# Sheet1.net
KiCad netlist of a schematic drawn in Altium Designer
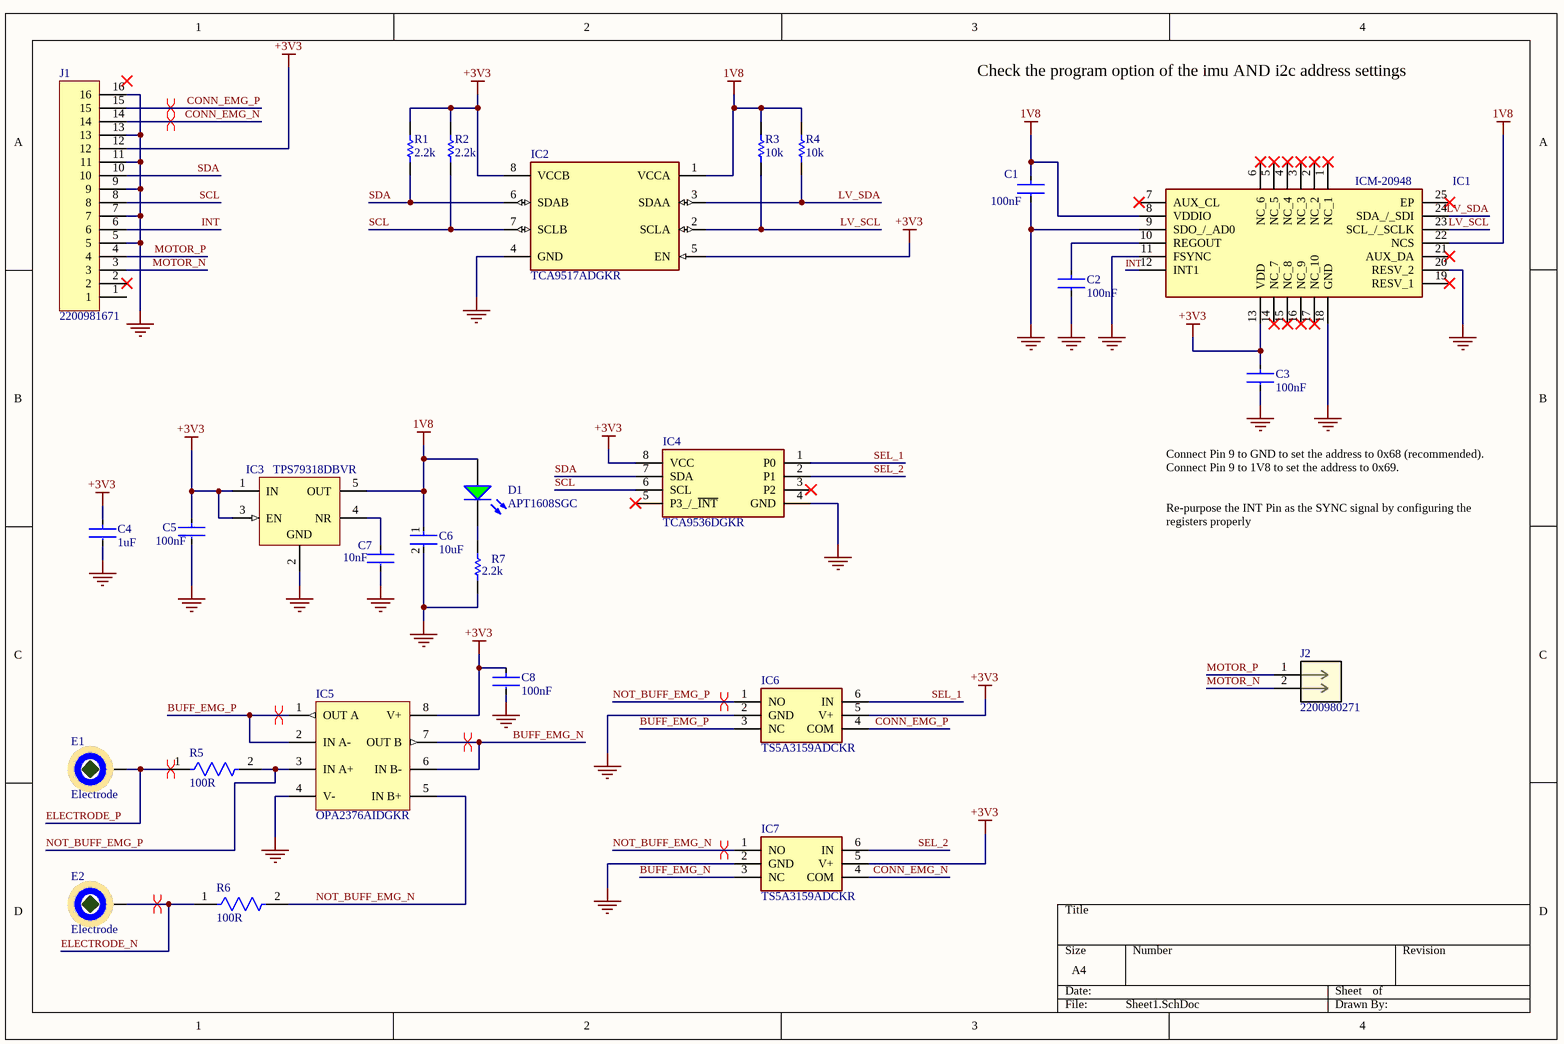
[diagram p0: Sheet1.SchDoc]

(export (version "E")
  (design (tool "Eeschema 10.0.6"))
  (components
    (comp (ref "C1")
      (value "100nF")
      (footprint "FP-CC0603-DA-MFG")
      (description "100nF 50V X7R ±10% 0603 Multilayer Ceramic Capacitors MLCC - SMD/SMT ROHS")
      (fields (field (name "MANUFACTURER") "YAGEO") (field (name "VOLTAGE") "50 V"))
      (libsource (lib "Altium Content Vault") (part "11868f565c42a9108669ba33697ecf6"))
    )
    (comp (ref "C2")
      (value "100nF")
      (footprint "FP-CC0603-DA-MFG")
      (description "100nF 50V X7R ±10% 0603 Multilayer Ceramic Capacitors MLCC - SMD/SMT ROHS")
      (fields (field (name "MANUFACTURER") "YAGEO") (field (name "VOLTAGE") "50 V"))
      (libsource (lib "Altium Content Vault") (part "11868f565c42a9108669ba33697ecf6"))
    )
    (comp (ref "C3")
      (value "100nF")
      (footprint "FP-CC0603-DA-MFG")
      (description "100nF 50V X7R ±10% 0603 Multilayer Ceramic Capacitors MLCC - SMD/SMT ROHS")
      (fields (field (name "MANUFACTURER") "YAGEO") (field (name "VOLTAGE") "50 V"))
      (libsource (lib "Altium Content Vault") (part "11868f565c42a9108669ba33697ecf6"))
    )
    (comp (ref "C4")
      (value "1uF")
      (footprint "FP-C0402C-BB-IPC_B")
      (description "CAP CER 1UF 16V X5R 0402")
      (fields (field (name "TOLERANCE") "10%") (field (name "MPN") "C0402C105K4PACTU"))
      (libsource (lib "Altium Content Vault") (part "b4654b650e69147ec39a6b967a45e02"))
    )
    (comp (ref "C5")
      (value "100nF")
      (footprint "FP-GRM155-0_05-MFG")
      (description "Chip Multilayer Ceramic Capacitors for General Purpose, 0402, 0.10uF, X7S, 22%, 10%, 50V")
      (fields (field (name "TOLERANCE") "10%") (field (name "MPN") "GRM155C71H104KE19D"))
      (libsource (lib "Altium Content Vault") (part "02cd4be3c70576c341d710602a673aa"))
    )
    (comp (ref "C6")
      (value "10uF")
      (footprint "FP-GRM155-0_2-IPC_A")
      (description "Chip Multilayer Ceramic Capacitors for General Purpose, 0402, 10uF, X5R, 15%, 20%, 10V")
      (fields (field (name "MPN") "GRM155R61A106ME11D"))
      (libsource (lib "") (part "b4654b650e69147ec39a6b967a45e02_1"))
    )
    (comp (ref "C7")
      (value "10nF")
      (footprint "FP-C0402-BB-MFG")
      (description "C0402 10,000 pF X7R 10.00% 50 V")
      (fields
        (field (name "OCTOPART") "https://octopart.com/c0402c103k5rac7411-kemet-25528449")
        (field (name "TOLERANCE") "0.1")
      )
      (libsource (lib "Altium Content Vault") (part "b4654b650e69147ec39a6b967a45e02"))
    )
    (comp (ref "C8")
      (value "100nF")
      (footprint "FP-CC0603-DA-MFG")
      (description "100nF 50V X7R ±10% 0603 Multilayer Ceramic Capacitors MLCC - SMD/SMT ROHS")
      (fields (field (name "MANUFACTURER") "YAGEO") (field (name "VOLTAGE") "50 V"))
      (libsource (lib "Altium Content Vault") (part "11868f565c42a9108669ba33697ecf6"))
    )
    (comp (ref "D1")
      (value "APT1608SGC")
      (footprint "KING-APT1608SGC_V")
      (description "Super Bright Green LED, 62.5 mW, 25 mA, -40 to 85 degC, 2-Pin SMD, RoHS, Tape and Reel")
      (fields (field (name "MANUFACTURER") "Kingbright"))
      (libsource (lib "Altium Content Vault") (part "LED-GREEN-AK-2"))
    )
    (comp (ref "E1")
      (value "Electrode")
      (footprint "Electrode")
      (libsource (lib "Sensor_node") (part "Electrode"))
    )
    (comp (ref "E2")
      (value "Electrode")
      (footprint "Electrode")
      (libsource (lib "Sensor_node") (part "Electrode"))
    )
    (comp (ref "IC1")
      (value "ICM-20948")
      (footprint "SamacSys:QFN40P300X300X105-25N-D")
      (description "Integrated Circuit")
      (fields (field (name "MOUSER PART NUMBER") "410-ICM-20948"))
      (libsource (lib "*") (part "ICM-20948"))
    )
    (comp (ref "IC2")
      (value "TCA9517ADGKR")
      (footprint "FP-DGK0008A-IPC_C")
      (description "IC TRNSLTR BIDIRECTIONAL 8VSSOP")
      (libsource (lib "Altium Content Vault") (part "376f503177af6135b4bcb823927ec01"))
    )
    (comp (ref "IC3")
      (value "TPS79318DBVR")
      (footprint "DBV0005A_M")
      (fields (field (name "MANUFACTURER") "Texas Instruments"))
      (libsource (lib "Altium Content Vault") (part "TI-TPS79NXX-YYSOT5"))
    )
    (comp (ref "IC4")
      (value "TCA9536DGKR")
      (footprint "SamacSys:SOP65P490X110-8N")
      (description "Integrated Circuit")
      (fields (field (name "MOUSER PART NUMBER") "595-TCA9536DGKR"))
      (libsource (lib "*") (part "TCA9536DGKR"))
    )
    (comp (ref "IC5")
      (value "OPA2376AIDGKR")
      (footprint "OPA2376")
      (description "IC OPAMP GP 2 CIRCUIT 8VSSOP")
      (libsource (lib "Sensor_node") (part "OPA2376AIDGKR"))
    )
    (comp (ref "IC6")
      (value "TS5A3159ADCKR")
      (footprint "SamacSys:SOT65P210X110-6N")
      (description "IC SWITCH SPDTX1 900MOHM SC70-6")
      (fields (field (name "MOUSER PART NUMBER") "595-TS5A3159ADCKR"))
      (libsource (lib "*") (part "TS5A3159ADCKR"))
    )
    (comp (ref "IC7")
      (value "TS5A3159ADCKR")
      (footprint "SamacSys:SOT65P210X110-6N")
      (description "IC SWITCH SPDTX1 900MOHM SC70-6")
      (fields (field (name "MOUSER PART NUMBER") "595-TS5A3159ADCKR"))
      (libsource (lib "*") (part "TS5A3159ADCKR"))
    )
    (comp (ref "J1")
      (value "2200981671")
      (footprint "CONN_2200980000-SD_16_MOL")
      (description "Connector Header Through Hole, Right Angle 16 position 0.049\" (1.25mm)")
      (libsource (lib "Sensor_node") (part "2200981671"))
    )
    (comp (ref "J2")
      (value "2200980271")
      (footprint "2X1_right_angle_THT_CON")
      (description "Molex connector")
      (libsource (lib "Sensor_node") (part "2X1_RHTANG_HDR"))
    )
    (comp (ref "R1")
      (value "2.2k")
      (footprint "RESC0402(1005)_N")
      (description "2K2 0.063W 5% 0402 (1005 Metric)  SMD")
      (fields (field (name "TOLERANCE") "5 %") (field (name "POWER") "0.063 W"))
      (libsource (lib "Altium Content Vault") (part "RES"))
    )
    (comp (ref "R2")
      (value "2.2k")
      (footprint "RESC0402(1005)_N")
      (description "2K2 0.063W 5% 0402 (1005 Metric)  SMD")
      (fields (field (name "TOLERANCE") "5 %") (field (name "POWER") "0.063 W"))
      (libsource (lib "Altium Content Vault") (part "RES"))
    )
    (comp (ref "R3")
      (value "10k")
      (footprint "RESC1005X40X20NL05T10")
      (fields
        (field (name "MANUFACTURER") "Vishay BCcomponents")
        (field (name "PART NUMBER") "TNPW040210K0DEED")
      )
      (libsource (lib "Altium Content Vault") (part "RES"))
    )
    (comp (ref "R4")
      (value "10k")
      (footprint "RESC1005X40X20NL05T10")
      (fields
        (field (name "MANUFACTURER") "Vishay BCcomponents")
        (field (name "PART NUMBER") "TNPW040210K0DEED")
      )
      (libsource (lib "Altium Content Vault") (part "RES"))
    )
    (comp (ref "R5")
      (value "100R")
      (footprint "FP-MCS0402-IPC_B")
      (description "RES SMD 1.2K OHM 1% 1/10W 0402")
      (fields (field (name "TOLERANCE") "0.5%") (field (name "MPN") "MCS0402MD1000DE000"))
      (libsource (lib "Altium Content Vault") (part "1029c3af85768c4190bb7ad29bc67b5"))
    )
    (comp (ref "R6")
      (value "100R")
      (footprint "FP-MCS0402-IPC_B")
      (description "RES SMD 1.2K OHM 1% 1/10W 0402")
      (fields (field (name "TOLERANCE") "0.5%") (field (name "MPN") "MCS0402MD1000DE000"))
      (libsource (lib "Altium Content Vault") (part "1029c3af85768c4190bb7ad29bc67b5"))
    )
    (comp (ref "R7")
      (value "2.2k")
      (footprint "RESC0402(1005)_N")
      (description "2K2 0.063W 5% 0402 (1005 Metric)  SMD")
      (fields (field (name "TOLERANCE") "5 %") (field (name "POWER") "0.063 W"))
      (libsource (lib "Altium Content Vault") (part "RES"))
    )
  )
  (nets
    (net (code "1") (name "+3V3") (class "Default")
      (node (ref "C3") (pin "1") (pinfunction "1_1") (pintype "passive"))
      (node (ref "C4") (pin "1") (pinfunction "1_1") (pintype "passive"))
      (node (ref "C5") (pin "1") (pinfunction "1_1") (pintype "passive"))
      (node (ref "C8") (pin "1") (pinfunction "1_1") (pintype "passive"))
      (node (ref "IC1") (pin "13") (pinfunction "VDD_13") (pintype "passive"))
      (node (ref "IC2") (pin "5") (pinfunction "EN_5") (pintype "input"))
      (node (ref "IC2") (pin "8") (pinfunction "VCCB_8") (pintype "power_in"))
      (node (ref "IC3") (pin "1") (pinfunction "IN_1") (pintype "power_in"))
      (node (ref "IC3") (pin "3") (pinfunction "EN_3") (pintype "input"))
      (node (ref "IC4") (pin "8") (pinfunction "VCC_8") (pintype "passive"))
      (node (ref "IC5") (pin "8") (pinfunction "V+_8") (pintype "power_in"))
      (node (ref "IC6") (pin "5") (pinfunction "V+_5") (pintype "passive"))
      (node (ref "IC7") (pin "5") (pinfunction "V+_5") (pintype "passive"))
      (node (ref "J1") (pin "12") (pinfunction "12_12") (pintype "passive"))
      (node (ref "R1") (pin "2") (pinfunction "2_2") (pintype "passive"))
      (node (ref "R2") (pin "2") (pinfunction "2_2") (pintype "passive"))
    )
    (net (code "2") (name "/BUFF_EMG_N") (class "Default")
      (node (ref "IC5") (pin "6") (pinfunction "IN_B-_6") (pintype "passive"))
      (node (ref "IC5") (pin "7") (pinfunction "OUT_B_7") (pintype "output"))
      (node (ref "IC7") (pin "3") (pinfunction "NC_3") (pintype "passive"))
    )
    (net (code "3") (name "/BUFF_EMG_P") (class "Default")
      (node (ref "IC5") (pin "1") (pinfunction "OUT_A_1") (pintype "output"))
      (node (ref "IC5") (pin "2") (pinfunction "IN_A-_2") (pintype "passive"))
      (node (ref "IC6") (pin "3") (pinfunction "NC_3") (pintype "passive"))
    )
    (net (code "4") (name "/CONN_EMG_N") (class "Default")
      (node (ref "IC7") (pin "4") (pinfunction "COM_4") (pintype "passive"))
      (node (ref "J1") (pin "14") (pinfunction "14_14") (pintype "passive"))
    )
    (net (code "5") (name "/CONN_EMG_P") (class "Default")
      (node (ref "IC6") (pin "4") (pinfunction "COM_4") (pintype "passive"))
      (node (ref "J1") (pin "15") (pinfunction "15_15") (pintype "passive"))
    )
    (net (code "6") (name "/ELECTRODE_N") (class "Default")
      (node (ref "E2") (pin "1") (pinfunction "1_1") (pintype "passive"))
      (node (ref "R6") (pin "1") (pinfunction "1_1") (pintype "passive"))
    )
    (net (code "7") (name "/ELECTRODE_P") (class "Default")
      (node (ref "E1") (pin "1") (pinfunction "1_1") (pintype "passive"))
      (node (ref "R5") (pin "1") (pinfunction "1_1") (pintype "passive"))
    )
    (net (code "8") (name "/INT") (class "Default")
      (node (ref "IC1") (pin "12") (pinfunction "INT1_12") (pintype "passive"))
      (node (ref "J1") (pin "6") (pinfunction "6_6") (pintype "passive"))
    )
    (net (code "9") (name "/LV_SCL") (class "Default")
      (node (ref "IC1") (pin "23") (pinfunction "SCL_/_SCLK_23") (pintype "passive"))
      (node (ref "IC2") (pin "2") (pinfunction "SCLA_2") (pintype "bidirectional"))
      (node (ref "R3") (pin "1") (pinfunction "1_1") (pintype "passive"))
    )
    (net (code "10") (name "/LV_SDA") (class "Default")
      (node (ref "IC1") (pin "24") (pinfunction "SDA_/_SDI_24") (pintype "passive"))
      (node (ref "IC2") (pin "3") (pinfunction "SDAA_3") (pintype "bidirectional"))
      (node (ref "R4") (pin "1") (pinfunction "1_1") (pintype "passive"))
    )
    (net (code "11") (name "/MOTOR_N") (class "Default")
      (node (ref "J1") (pin "3") (pinfunction "3_3") (pintype "passive"))
      (node (ref "J2") (pin "2") (pinfunction "2_2") (pintype "passive"))
    )
    (net (code "12") (name "/MOTOR_P") (class "Default")
      (node (ref "J1") (pin "4") (pinfunction "4_4") (pintype "passive"))
      (node (ref "J2") (pin "1") (pinfunction "1_1") (pintype "passive"))
    )
    (net (code "13") (name "/NOT_BUFF_EMG_N") (class "Default")
      (node (ref "IC5") (pin "5") (pinfunction "IN_B+_5") (pintype "passive"))
      (node (ref "IC7") (pin "1") (pinfunction "NO_1") (pintype "passive"))
      (node (ref "R6") (pin "2") (pinfunction "2_2") (pintype "passive"))
    )
    (net (code "14") (name "/NOT_BUFF_EMG_P") (class "Default")
      (node (ref "IC5") (pin "3") (pinfunction "IN_A+_3") (pintype "passive"))
      (node (ref "IC6") (pin "1") (pinfunction "NO_1") (pintype "passive"))
      (node (ref "R5") (pin "2") (pinfunction "2_2") (pintype "passive"))
    )
    (net (code "15") (name "/SCL") (class "Default")
      (node (ref "IC2") (pin "7") (pinfunction "SCLB_7") (pintype "bidirectional"))
      (node (ref "IC4") (pin "6") (pinfunction "SCL_6") (pintype "passive"))
      (node (ref "J1") (pin "8") (pinfunction "8_8") (pintype "passive"))
      (node (ref "R2") (pin "1") (pinfunction "1_1") (pintype "passive"))
    )
    (net (code "16") (name "/SDA") (class "Default")
      (node (ref "IC2") (pin "6") (pinfunction "SDAB_6") (pintype "bidirectional"))
      (node (ref "IC4") (pin "7") (pinfunction "SDA_7") (pintype "passive"))
      (node (ref "J1") (pin "10") (pinfunction "10_10") (pintype "passive"))
      (node (ref "R1") (pin "1") (pinfunction "1_1") (pintype "passive"))
    )
    (net (code "17") (name "/SEL_1") (class "Default")
      (node (ref "IC4") (pin "1") (pinfunction "P0_1") (pintype "passive"))
      (node (ref "IC6") (pin "6") (pinfunction "IN_6") (pintype "passive"))
    )
    (net (code "18") (name "/SEL_2") (class "Default")
      (node (ref "IC4") (pin "2") (pinfunction "P1_2") (pintype "passive"))
      (node (ref "IC7") (pin "6") (pinfunction "IN_6") (pintype "passive"))
    )
    (net (code "19") (name "1V8") (class "Default")
      (node (ref "C1") (pin "1") (pinfunction "1_1") (pintype "passive"))
      (node (ref "C6") (pin "1") (pinfunction "1_1") (pintype "passive"))
      (node (ref "D1") (pin "1") (pinfunction "A_1") (pintype "passive"))
      (node (ref "IC1") (pin "22") (pinfunction "NCS_22") (pintype "passive"))
      (node (ref "IC1") (pin "8") (pinfunction "VDDIO_8") (pintype "passive"))
      (node (ref "IC2") (pin "1") (pinfunction "VCCA_1") (pintype "power_in"))
      (node (ref "IC3") (pin "5") (pinfunction "OUT_5") (pintype "power_in"))
      (node (ref "R3") (pin "2") (pinfunction "2_2") (pintype "passive"))
      (node (ref "R4") (pin "2") (pinfunction "2_2") (pintype "passive"))
    )
    (net (code "20") (name "GND") (class "Default")
      (node (ref "C1") (pin "2") (pinfunction "2_2") (pintype "passive"))
      (node (ref "C2") (pin "2") (pinfunction "2_2") (pintype "passive"))
      (node (ref "C3") (pin "2") (pinfunction "2_2") (pintype "passive"))
      (node (ref "C4") (pin "2") (pinfunction "2_2") (pintype "passive"))
      (node (ref "C5") (pin "2") (pinfunction "2_2") (pintype "passive"))
      (node (ref "C6") (pin "2") (pinfunction "2_2") (pintype "passive"))
      (node (ref "C7") (pin "2") (pinfunction "2_2") (pintype "passive"))
      (node (ref "C8") (pin "2") (pinfunction "2_2") (pintype "passive"))
      (node (ref "IC1") (pin "11") (pinfunction "FSYNC_11") (pintype "passive"))
      (node (ref "IC1") (pin "18") (pinfunction "GND_18") (pintype "passive"))
      (node (ref "IC1") (pin "20") (pinfunction "RESV_2_20") (pintype "passive"))
      (node (ref "IC1") (pin "9") (pinfunction "SDO_/_AD0_9") (pintype "passive"))
      (node (ref "IC2") (pin "4") (pinfunction "GND_4") (pintype "power_in"))
      (node (ref "IC3") (pin "2") (pinfunction "GND_2") (pintype "power_in"))
      (node (ref "IC4") (pin "4") (pinfunction "GND_4") (pintype "passive"))
      (node (ref "IC5") (pin "4") (pinfunction "V-_4") (pintype "power_in"))
      (node (ref "IC6") (pin "2") (pinfunction "GND_2") (pintype "passive"))
      (node (ref "IC7") (pin "2") (pinfunction "GND_2") (pintype "passive"))
      (node (ref "J1") (pin "11") (pinfunction "11_11") (pintype "passive"))
      (node (ref "J1") (pin "13") (pinfunction "13_13") (pintype "passive"))
      (node (ref "J1") (pin "16") (pinfunction "16_16") (pintype "passive"))
      (node (ref "J1") (pin "5") (pinfunction "5_5") (pintype "passive"))
      (node (ref "J1") (pin "7") (pinfunction "7_7") (pintype "passive"))
      (node (ref "J1") (pin "9") (pinfunction "9_9") (pintype "passive"))
      (node (ref "R7") (pin "1") (pinfunction "1_1") (pintype "passive"))
    )
    (net (code "21") (name "Net-(D1-K)") (class "Default")
      (node (ref "D1") (pin "2") (pinfunction "K_2") (pintype "passive"))
      (node (ref "R7") (pin "2") (pinfunction "2_2") (pintype "passive"))
    )
    (net (code "22") (name "Net-(IC1-REGOUT)") (class "Default")
      (node (ref "C2") (pin "1") (pinfunction "1_1") (pintype "passive"))
      (node (ref "IC1") (pin "10") (pinfunction "REGOUT_10") (pintype "passive"))
    )
    (net (code "23") (name "Net-(IC3-NR)") (class "Default")
      (node (ref "C7") (pin "1") (pinfunction "1_1") (pintype "passive"))
      (node (ref "IC3") (pin "4") (pinfunction "NR_4") (pintype "passive"))
    )
    (net (code "24") (name "unconnected-(IC1-AUX_CL-Pad7)") (class "Default")
      (node (ref "IC1") (pin "7") (pinfunction "AUX_CL_7") (pintype "passive+no_connect"))
    )
    (net (code "25") (name "unconnected-(IC1-AUX_DA-Pad21)") (class "Default")
      (node (ref "IC1") (pin "21") (pinfunction "AUX_DA_21") (pintype "passive+no_connect"))
    )
    (net (code "26") (name "unconnected-(IC1-EP-Pad25)") (class "Default")
      (node (ref "IC1") (pin "25") (pinfunction "EP_25") (pintype "passive+no_connect"))
    )
    (net (code "27") (name "unconnected-(IC1-NC_1-Pad1)") (class "Default")
      (node (ref "IC1") (pin "1") (pinfunction "NC_1_1") (pintype "passive+no_connect"))
    )
    (net (code "28") (name "unconnected-(IC1-NC_2-Pad2)") (class "Default")
      (node (ref "IC1") (pin "2") (pinfunction "NC_2_2") (pintype "passive+no_connect"))
    )
    (net (code "29") (name "unconnected-(IC1-NC_3-Pad3)") (class "Default")
      (node (ref "IC1") (pin "3") (pinfunction "NC_3_3") (pintype "passive+no_connect"))
    )
    (net (code "30") (name "unconnected-(IC1-NC_4-Pad4)") (class "Default")
      (node (ref "IC1") (pin "4") (pinfunction "NC_4_4") (pintype "passive+no_connect"))
    )
    (net (code "31") (name "unconnected-(IC1-NC_5-Pad5)") (class "Default")
      (node (ref "IC1") (pin "5") (pinfunction "NC_5_5") (pintype "passive+no_connect"))
    )
    (net (code "32") (name "unconnected-(IC1-NC_6-Pad6)") (class "Default")
      (node (ref "IC1") (pin "6") (pinfunction "NC_6_6") (pintype "passive+no_connect"))
    )
    (net (code "33") (name "unconnected-(IC1-NC_7-Pad14)") (class "Default")
      (node (ref "IC1") (pin "14") (pinfunction "NC_7_14") (pintype "passive+no_connect"))
    )
    (net (code "34") (name "unconnected-(IC1-NC_8-Pad15)") (class "Default")
      (node (ref "IC1") (pin "15") (pinfunction "NC_8_15") (pintype "passive+no_connect"))
    )
    (net (code "35") (name "unconnected-(IC1-NC_9-Pad16)") (class "Default")
      (node (ref "IC1") (pin "16") (pinfunction "NC_9_16") (pintype "passive+no_connect"))
    )
    (net (code "36") (name "unconnected-(IC1-NC_10-Pad17)") (class "Default")
      (node (ref "IC1") (pin "17") (pinfunction "NC_10_17") (pintype "passive+no_connect"))
    )
    (net (code "37") (name "unconnected-(IC1-RESV_1-Pad19)") (class "Default")
      (node (ref "IC1") (pin "19") (pinfunction "RESV_1_19") (pintype "passive+no_connect"))
    )
    (net (code "38") (name "unconnected-(IC4-P2-Pad3)") (class "Default")
      (node (ref "IC4") (pin "3") (pinfunction "P2_3") (pintype "passive+no_connect"))
    )
    (net (code "39") (name "unconnected-(IC4-P3_{slash}_~{INT}-Pad5)") (class "Default")
      (node (ref "IC4") (pin "5") (pinfunction "P3_/_~{INT}_5") (pintype "passive+no_connect"))
    )
    (net (code "40") (name "unconnected-(J1-Pad1)") (class "Default")
      (node (ref "J1") (pin "1") (pinfunction "1_1") (pintype "passive"))
    )
    (net (code "41") (name "unconnected-(J1-Pad2)") (class "Default")
      (node (ref "J1") (pin "2") (pinfunction "2_2") (pintype "passive+no_connect"))
    )
  )
)
